# tomu-eagle1.net
KiCad netlist of a schematic drawn in EAGLE
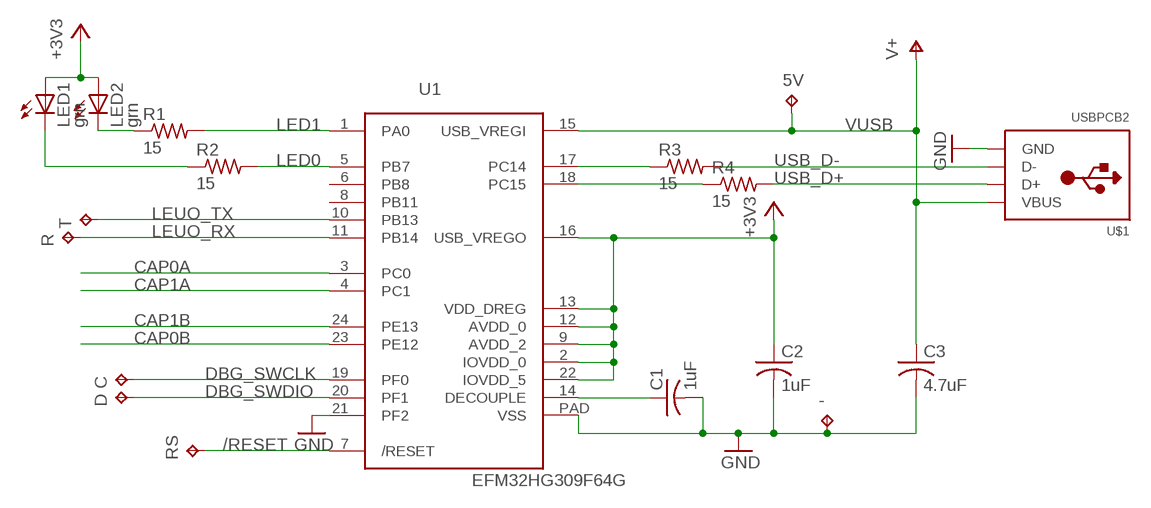
[diagram p0: schematic, sheet 1]

(export (version "E")
  (design (tool "Eeschema 10.0.6"))
  (components
    (comp (ref "-")
      (value "TPTP10SQ")
      (footprint "eagle-import:TP10SQ")
      (libsource (lib "eagle-import") (part "TPTP10SQ"))
    )
    (comp (ref "5V")
      (value "TPTP10R")
      (footprint "eagle-import:TP10R")
      (libsource (lib "eagle-import") (part "TPTP10R"))
    )
    (comp (ref "C")
      (value "TPTP10R")
      (footprint "eagle-import:TP10R")
      (libsource (lib "eagle-import") (part "TPTP10R"))
    )
    (comp (ref "C1")
      (value "1uF")
      (footprint "eagle-import:C0402")
      (libsource (lib "eagle-import") (part "C-USC0402"))
    )
    (comp (ref "C2")
      (value "1uF")
      (footprint "eagle-import:C0402")
      (libsource (lib "eagle-import") (part "C-USC0402"))
    )
    (comp (ref "C3")
      (value "4.7uF")
      (footprint "eagle-import:C0402")
      (libsource (lib "eagle-import") (part "C-USC0402"))
    )
    (comp (ref "D")
      (value "TPTP10R")
      (footprint "eagle-import:TP10R")
      (libsource (lib "eagle-import") (part "TPTP10R"))
    )
    (comp (ref "LED1")
      (value "grn")
      (footprint "eagle-import:CHIP-LED0603")
      (libsource (lib "eagle-import") (part "LEDCHIP-LED0603"))
    )
    (comp (ref "LED2")
      (value "grn")
      (footprint "eagle-import:CHIP-LED0603")
      (libsource (lib "eagle-import") (part "LEDCHIP-LED0603"))
    )
    (comp (ref "R")
      (value "TPTP10R")
      (footprint "eagle-import:TP10R")
      (libsource (lib "eagle-import") (part "TPTP10R"))
    )
    (comp (ref "R1")
      (value "15")
      (footprint "eagle-import:R0402")
      (libsource (lib "eagle-import") (part "R-US_R0402"))
    )
    (comp (ref "R2")
      (value "15")
      (footprint "eagle-import:R0402")
      (libsource (lib "eagle-import") (part "R-US_R0402"))
    )
    (comp (ref "R3")
      (value "15")
      (footprint "eagle-import:R0402")
      (libsource (lib "eagle-import") (part "R-US_R0402"))
    )
    (comp (ref "R4")
      (value "15")
      (footprint "eagle-import:R0402")
      (libsource (lib "eagle-import") (part "R-US_R0402"))
    )
    (comp (ref "RS")
      (value "TPTP10R")
      (footprint "eagle-import:TP10R")
      (libsource (lib "eagle-import") (part "TPTP10R"))
    )
    (comp (ref "T")
      (value "TPTP10R")
      (footprint "eagle-import:TP10R")
      (libsource (lib "eagle-import") (part "TPTP10R"))
    )
    (comp (ref "U$1")
      (value "USBPCB2")
      (footprint "eagle-import:USB-A-PCB-2")
      (libsource (lib "eagle-import") (part "USBPCB2"))
    )
    (comp (ref "U1")
      (value "EFM32HG309F64G")
      (footprint "eagle-import:QFN24PAD")
      (libsource (lib "eagle-import") (part "EFM32HG309F64G"))
    )
  )
  (nets
    (net (code "1") (name "+3V3") (class "Default")
      (node (ref "C2") (pin "1") (pinfunction "1_1") (pintype "passive"))
      (node (ref "LED1") (pin "A") (pinfunction "A_A") (pintype "passive"))
      (node (ref "LED2") (pin "A") (pinfunction "A_A") (pintype "passive"))
      (node (ref "U1") (pin "12") (pinfunction "AVDD_0_12") (pintype "bidirectional"))
      (node (ref "U1") (pin "13") (pinfunction "VDD_DREG_13") (pintype "bidirectional"))
      (node (ref "U1") (pin "16") (pinfunction "USB_VREGO_16") (pintype "bidirectional"))
      (node (ref "U1") (pin "2") (pinfunction "IOVDD_0_2") (pintype "bidirectional"))
      (node (ref "U1") (pin "22") (pinfunction "IOVDD_5_22") (pintype "bidirectional"))
      (node (ref "U1") (pin "9") (pinfunction "AVDD_2_9") (pintype "bidirectional"))
    )
    (net (code "2") (name "/CAP0A") (class "Default")
      (node (ref "U1") (pin "3") (pinfunction "PC0_3") (pintype "bidirectional"))
    )
    (net (code "3") (name "/CAP0B") (class "Default")
      (node (ref "U1") (pin "23") (pinfunction "PE12_23") (pintype "bidirectional"))
    )
    (net (code "4") (name "/CAP1A") (class "Default")
      (node (ref "U1") (pin "4") (pinfunction "PC1_4") (pintype "bidirectional"))
    )
    (net (code "5") (name "/CAP1B") (class "Default")
      (node (ref "U1") (pin "24") (pinfunction "PE13_24") (pintype "bidirectional"))
    )
    (net (code "6") (name "/DBG_SWCLK") (class "Default")
      (node (ref "C") (pin "TP") (pinfunction "TP_TP") (pintype "input"))
      (node (ref "U1") (pin "19") (pinfunction "PF0_19") (pintype "bidirectional"))
    )
    (net (code "7") (name "/DBG_SWDIO") (class "Default")
      (node (ref "D") (pin "TP") (pinfunction "TP_TP") (pintype "input"))
      (node (ref "U1") (pin "20") (pinfunction "PF1_20") (pintype "bidirectional"))
    )
    (net (code "8") (name "/LED0") (class "Default")
      (node (ref "R2") (pin "2") (pinfunction "2_2") (pintype "passive"))
      (node (ref "U1") (pin "5") (pinfunction "PB7_5") (pintype "bidirectional"))
    )
    (net (code "9") (name "/LED1") (class "Default")
      (node (ref "R1") (pin "2") (pinfunction "2_2") (pintype "passive"))
      (node (ref "U1") (pin "1") (pinfunction "PA0_1") (pintype "bidirectional"))
    )
    (net (code "10") (name "/LEUO_RX") (class "Default")
      (node (ref "R") (pin "TP") (pinfunction "TP_TP") (pintype "input"))
      (node (ref "U1") (pin "11") (pinfunction "PB14_11") (pintype "bidirectional"))
    )
    (net (code "11") (name "/LEUO_TX") (class "Default")
      (node (ref "T") (pin "TP") (pinfunction "TP_TP") (pintype "input"))
      (node (ref "U1") (pin "10") (pinfunction "PB13_10") (pintype "bidirectional"))
    )
    (net (code "12") (name "/USB_D+") (class "Default")
      (node (ref "R4") (pin "2") (pinfunction "2_2") (pintype "passive"))
      (node (ref "U$1") (pin "USB_P") (pinfunction "D+_USB_P") (pintype "bidirectional"))
    )
    (net (code "13") (name "/USB_D-") (class "Default")
      (node (ref "R3") (pin "2") (pinfunction "2_2") (pintype "passive"))
      (node (ref "U$1") (pin "USB_M") (pinfunction "D-_USB_M") (pintype "bidirectional"))
    )
    (net (code "14") (name "/{slash}RESET") (class "Default")
      (node (ref "RS") (pin "TP") (pinfunction "TP_TP") (pintype "input"))
      (node (ref "U1") (pin "7") (pinfunction "/RESET_7") (pintype "bidirectional"))
    )
    (net (code "15") (name "GND") (class "Default")
      (node (ref "-") (pin "TP") (pinfunction "TP_TP") (pintype "input"))
      (node (ref "C1") (pin "2") (pinfunction "2_2") (pintype "passive"))
      (node (ref "C2") (pin "2") (pinfunction "2_2") (pintype "passive"))
      (node (ref "C3") (pin "2") (pinfunction "2_2") (pintype "passive"))
      (node (ref "U$1") (pin "GND") (pinfunction "GND_GND") (pintype "power_in"))
      (node (ref "U1") (pin "21") (pinfunction "PF2_21") (pintype "bidirectional"))
      (node (ref "U1") (pin "PAD") (pinfunction "VSS_PAD") (pintype "bidirectional"))
    )
    (net (code "16") (name "Net-(LED1-PadC)") (class "Default")
      (node (ref "LED1") (pin "C") (pinfunction "C_C") (pintype "passive"))
      (node (ref "R2") (pin "1") (pinfunction "1_1") (pintype "passive"))
    )
    (net (code "17") (name "Net-(LED2-PadC)") (class "Default")
      (node (ref "LED2") (pin "C") (pinfunction "C_C") (pintype "passive"))
      (node (ref "R1") (pin "1") (pinfunction "1_1") (pintype "passive"))
    )
    (net (code "18") (name "Net-(U1-DECOUPLE)") (class "Default")
      (node (ref "C1") (pin "1") (pinfunction "1_1") (pintype "passive"))
      (node (ref "U1") (pin "14") (pinfunction "DECOUPLE_14") (pintype "bidirectional"))
    )
    (net (code "19") (name "Net-(U1-PC14)") (class "Default")
      (node (ref "R3") (pin "1") (pinfunction "1_1") (pintype "passive"))
      (node (ref "U1") (pin "17") (pinfunction "PC14_17") (pintype "bidirectional"))
    )
    (net (code "20") (name "Net-(U1-PC15)") (class "Default")
      (node (ref "R4") (pin "1") (pinfunction "1_1") (pintype "passive"))
      (node (ref "U1") (pin "18") (pinfunction "PC15_18") (pintype "bidirectional"))
    )
    (net (code "21") (name "V+") (class "Default")
      (node (ref "5V") (pin "TP") (pinfunction "TP_TP") (pintype "input"))
      (node (ref "C3") (pin "1") (pinfunction "1_1") (pintype "passive"))
      (node (ref "U$1") (pin "5V") (pinfunction "VBUS_5V") (pintype "power_in"))
      (node (ref "U1") (pin "15") (pinfunction "USB_VREGI_15") (pintype "bidirectional"))
    )
    (net (code "22") (name "unconnected-(U1-PB8-Pad6)") (class "Default")
      (node (ref "U1") (pin "6") (pinfunction "PB8_6") (pintype "bidirectional"))
    )
    (net (code "23") (name "unconnected-(U1-PB11-Pad8)") (class "Default")
      (node (ref "U1") (pin "8") (pinfunction "PB11_8") (pintype "bidirectional"))
    )
  )
)
